# Servo2015_Power_V1_2.net
KiCad netlist of a schematic drawn in EAGLE
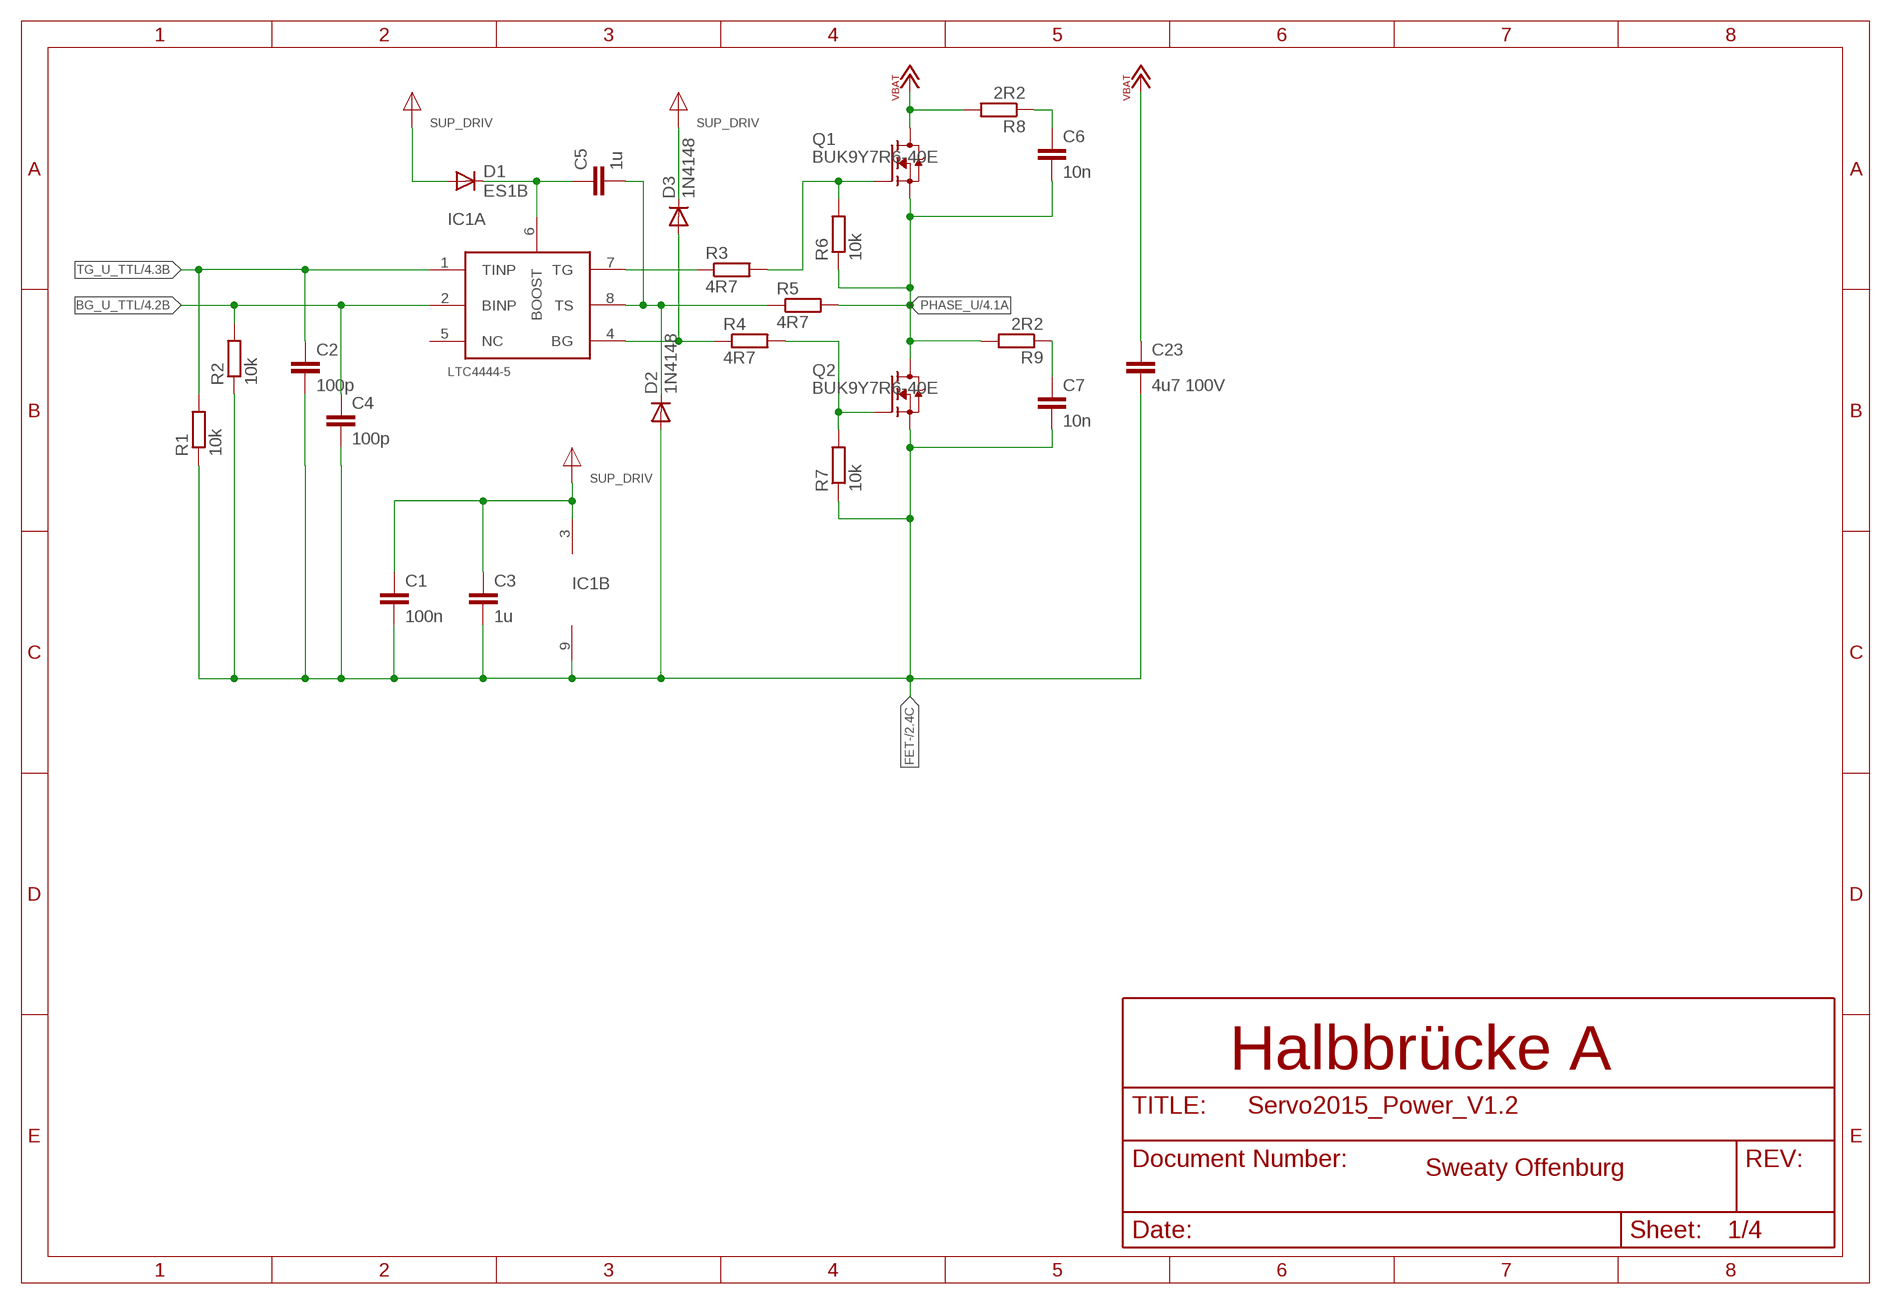
[diagram p0: schematic, sheet 1]
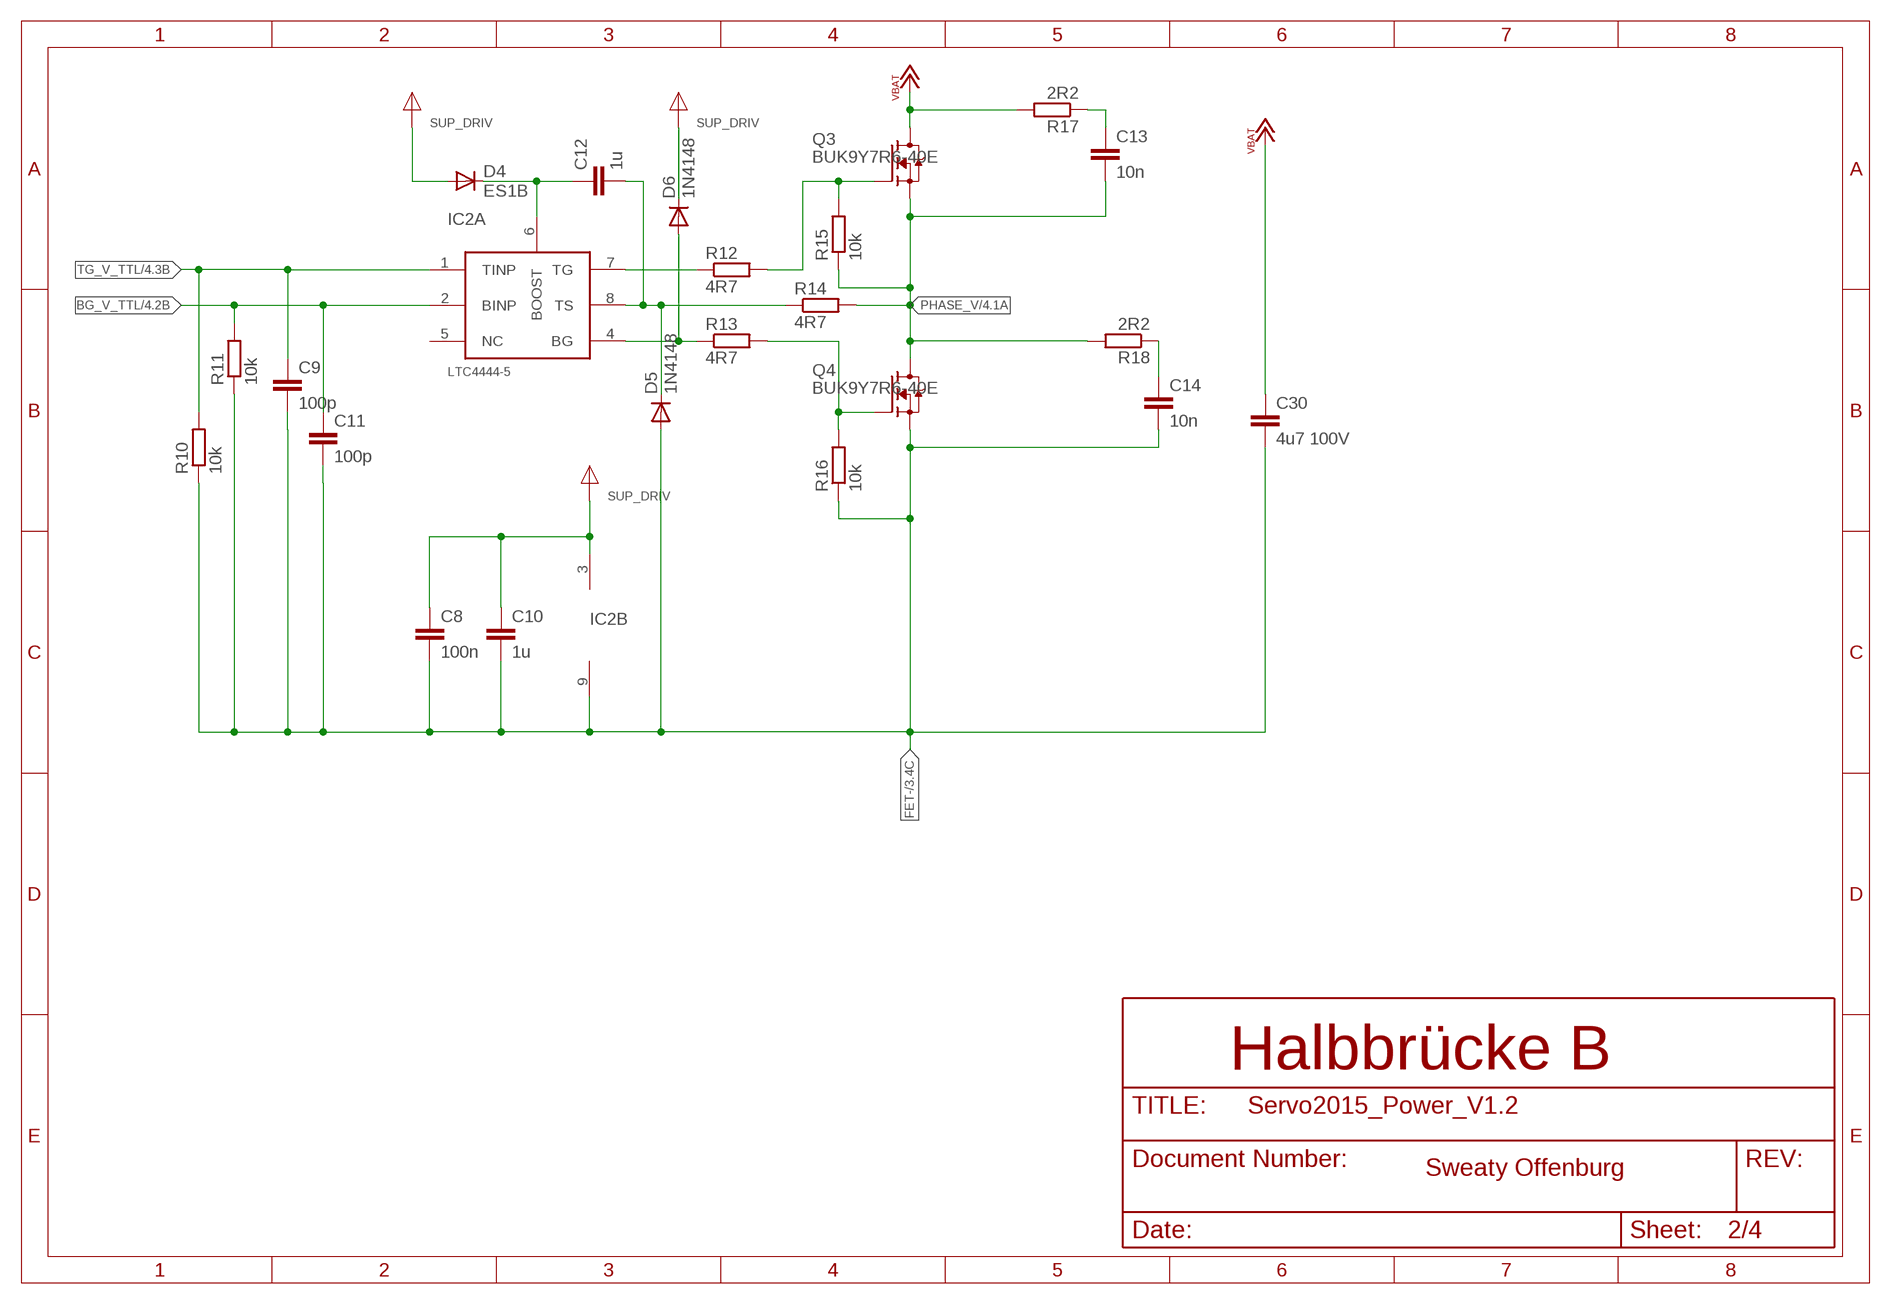
[diagram p1: schematic, sheet 2]
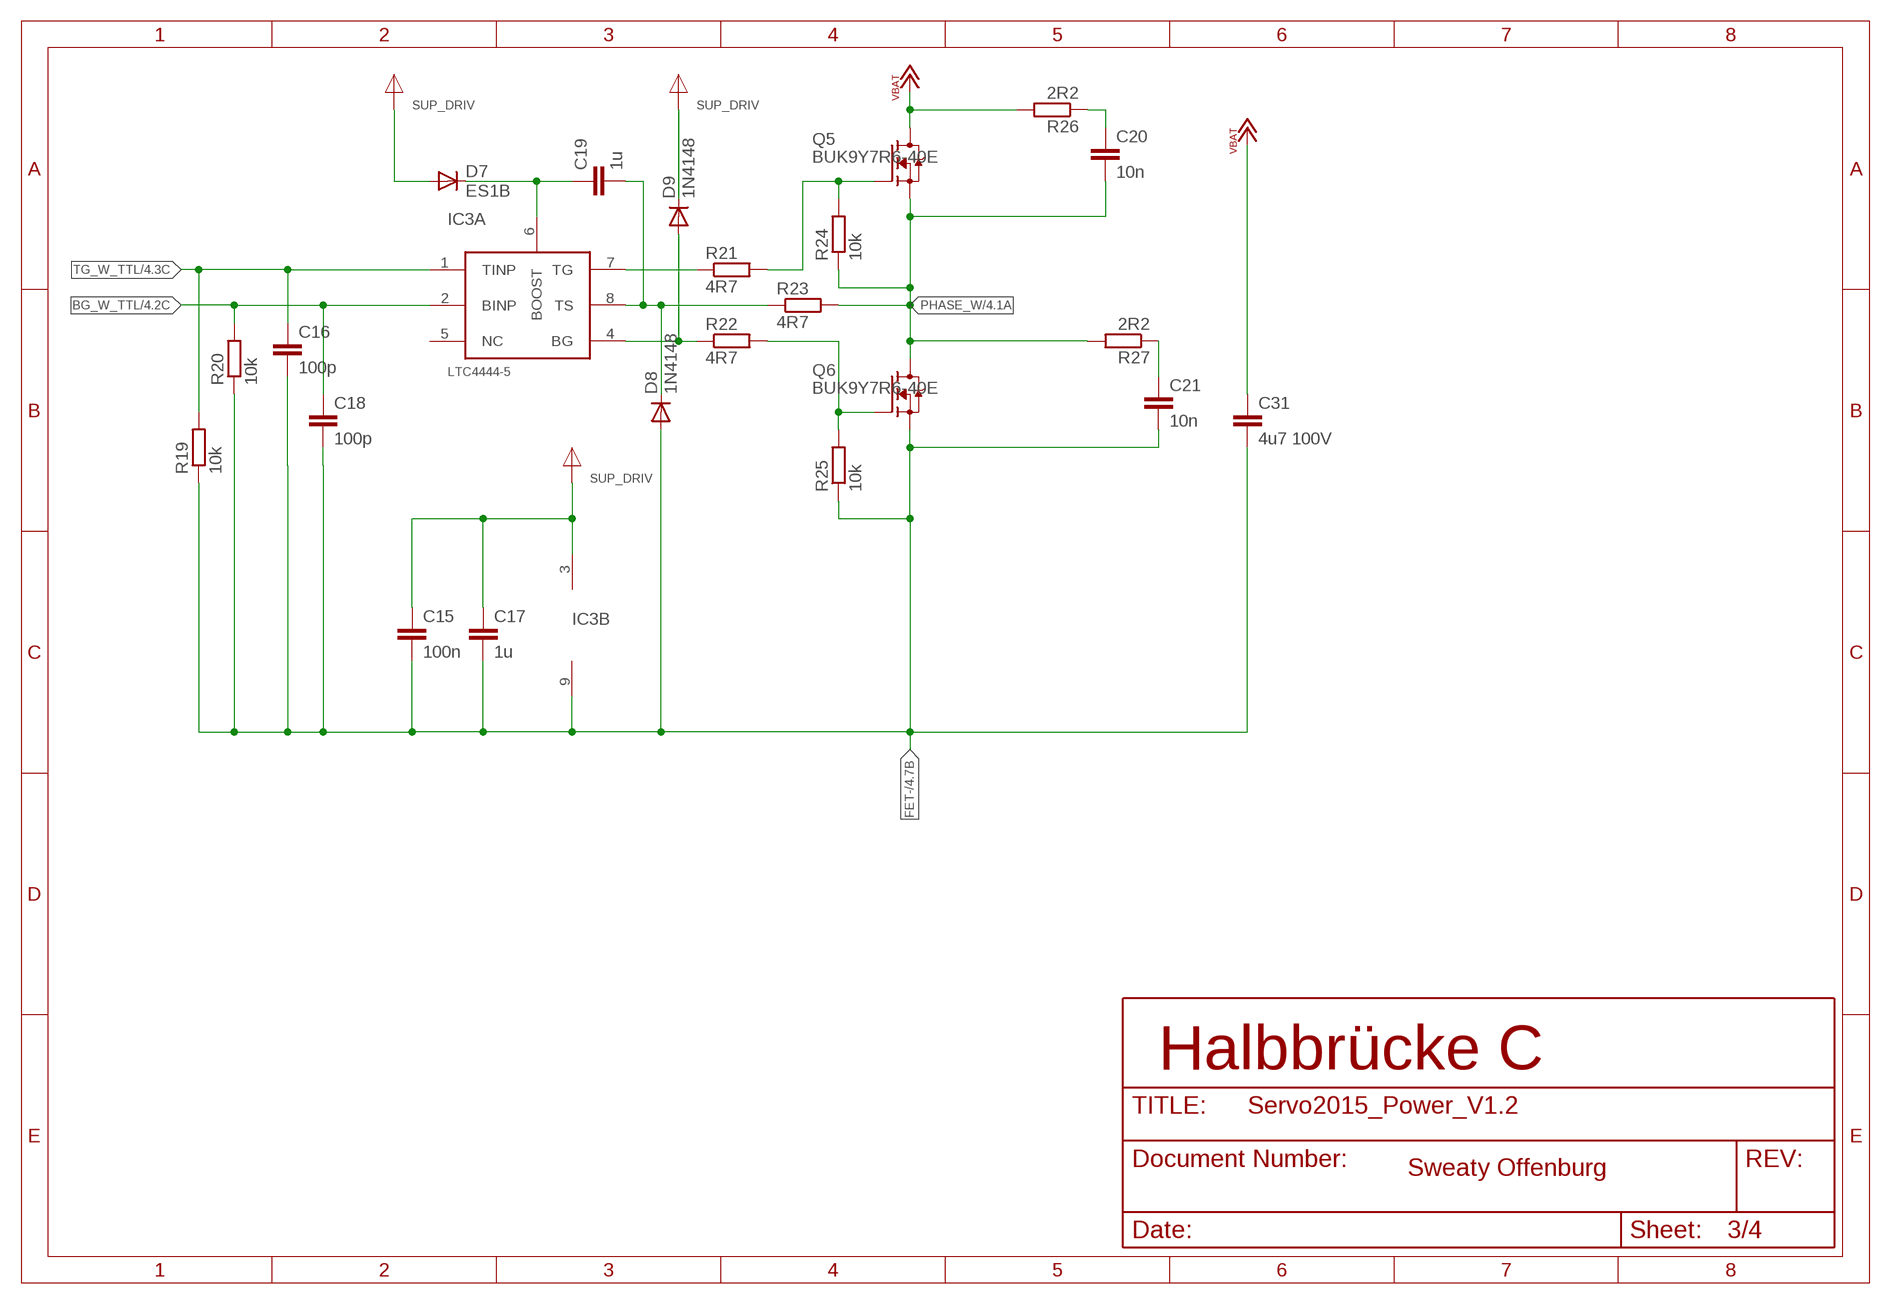
[diagram p2: schematic, sheet 3]
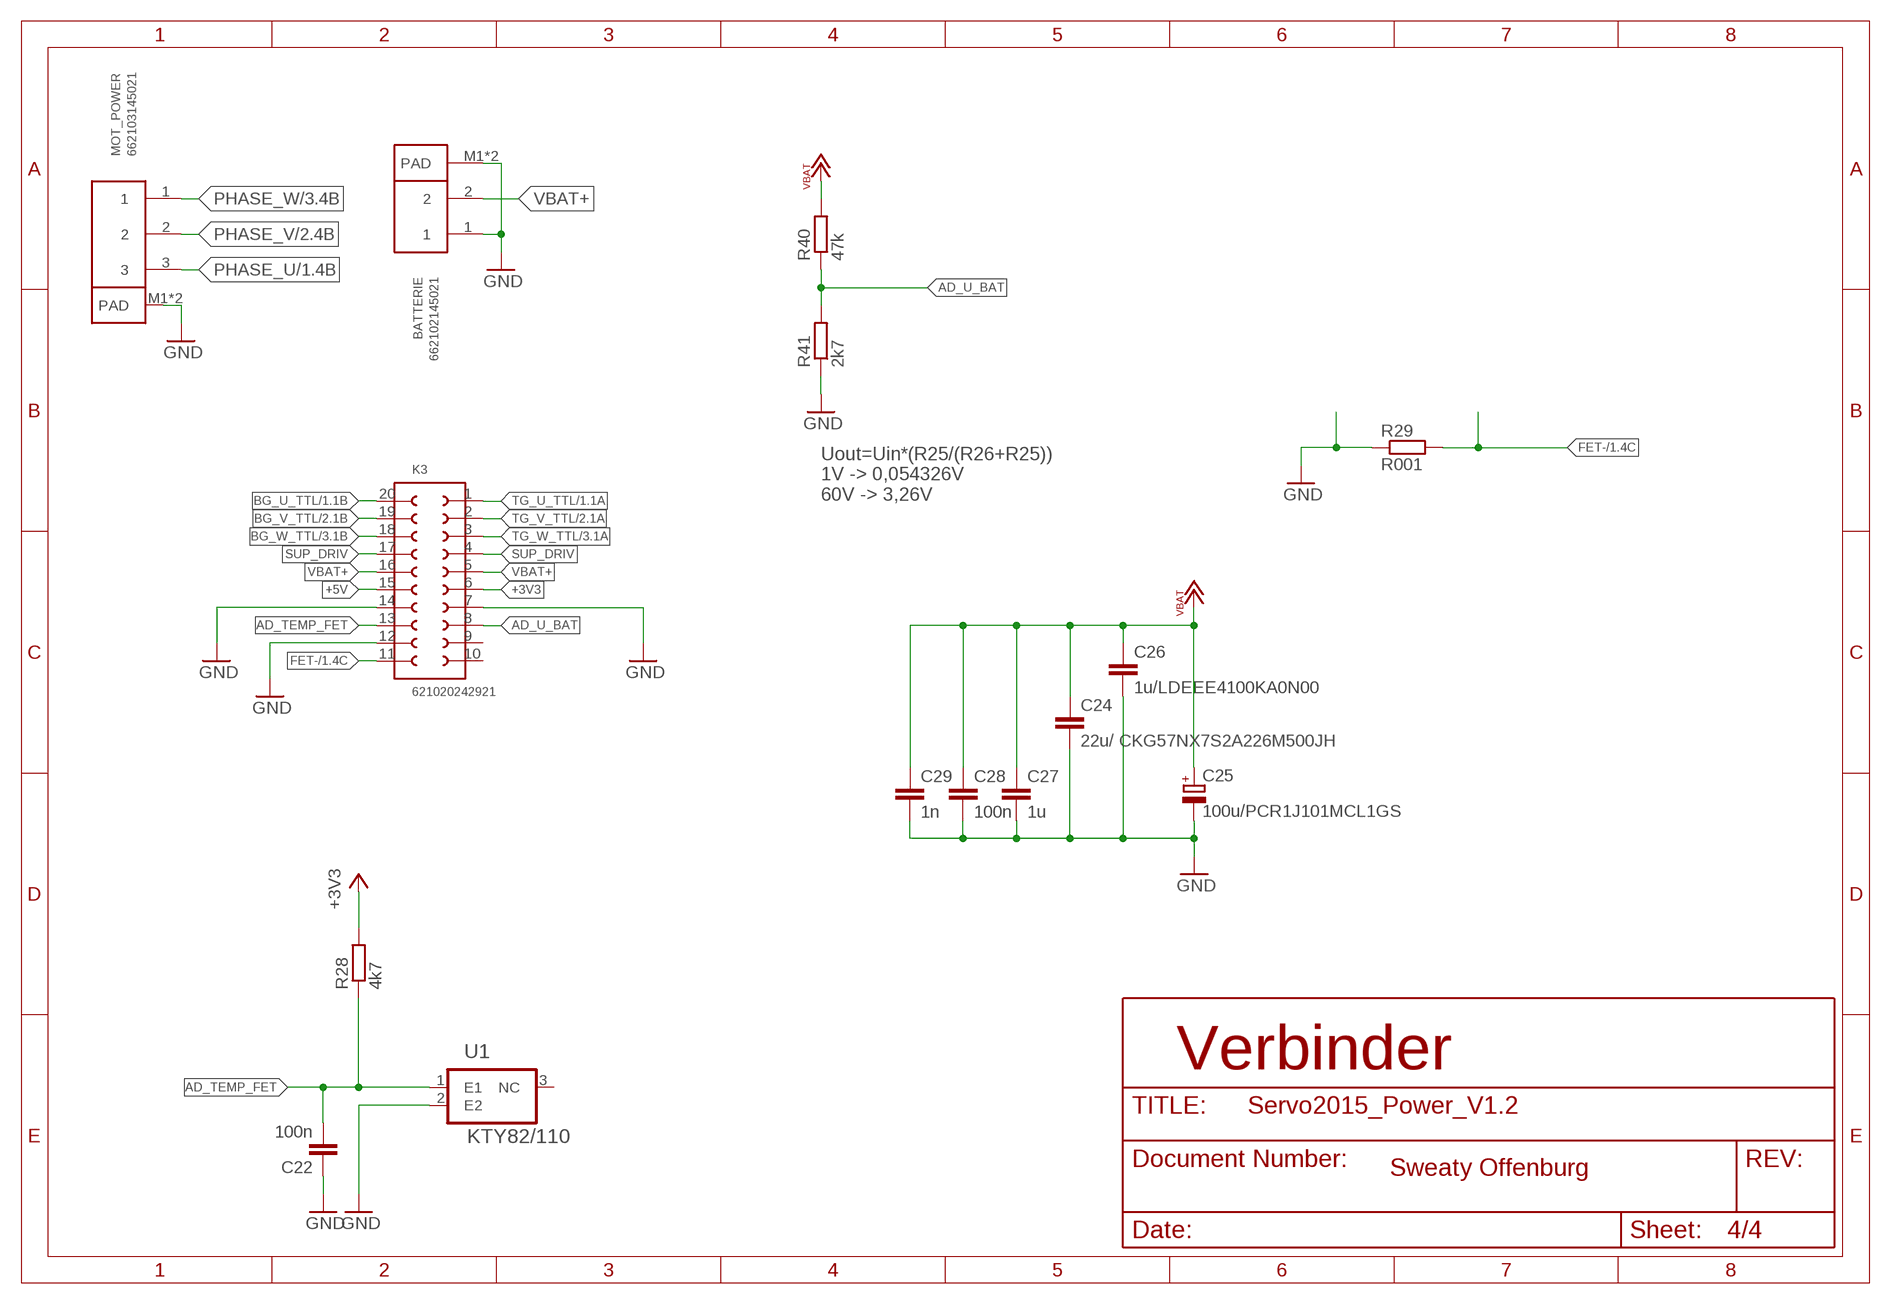
[diagram p3: schematic, sheet 4]

(export (version "E")
  (design (tool "Eeschema 10.0.6"))
  (components
    (comp (ref "C1")
      (value "100n")
      (footprint "eagle-import:C0603")
      (libsource (lib "eagle-import") (part "C-EUC0603"))
    )
    (comp (ref "C2")
      (value "100p")
      (footprint "eagle-import:C0603")
      (libsource (lib "eagle-import") (part "C-EUC0603"))
    )
    (comp (ref "C3")
      (value "1u")
      (footprint "eagle-import:C0603")
      (libsource (lib "eagle-import") (part "C-EUC0603"))
    )
    (comp (ref "C4")
      (value "100p")
      (footprint "eagle-import:C0603")
      (libsource (lib "eagle-import") (part "C-EUC0603"))
    )
    (comp (ref "C5")
      (value "1u")
      (footprint "eagle-import:C0603")
      (libsource (lib "eagle-import") (part "C-EUC0603"))
    )
    (comp (ref "C6")
      (value "10n")
      (footprint "eagle-import:C1210")
      (libsource (lib "eagle-import") (part "C-EUC1210"))
    )
    (comp (ref "C7")
      (value "10n")
      (footprint "eagle-import:C1210")
      (libsource (lib "eagle-import") (part "C-EUC1210"))
    )
    (comp (ref "C23")
      (value "4u7 100V")
      (footprint "eagle-import:C2220K")
      (libsource (lib "eagle-import") (part "C-EUC2220K"))
    )
    (comp (ref "D1")
      (value "ES1B")
      (footprint "eagle-import:DO214AC")
      (libsource (lib "eagle-import") (part "DIODE-DO214AC"))
    )
    (comp (ref "D2")
      (value "1N4148")
      (footprint "eagle-import:SOD123")
      (libsource (lib "eagle-import") (part "DIODE-SOD123"))
    )
    (comp (ref "D3")
      (value "1N4148")
      (footprint "eagle-import:SOD123")
      (libsource (lib "eagle-import") (part "DIODE-SOD123"))
    )
    (comp (ref "IC1")
      (value "LTC4444-5")
      (footprint "eagle-import:MS8E")
      (libsource (lib "eagle-import") (part "LTC4444-5"))
    )
    (comp (ref "Q1")
      (value "BUK9Y7R6-40E")
      (footprint "eagle-import:LFPAK56")
      (libsource (lib "eagle-import") (part "BUK9Y7R6-40E"))
    )
    (comp (ref "Q2")
      (value "BUK9Y7R6-40E")
      (footprint "eagle-import:LFPAK56")
      (libsource (lib "eagle-import") (part "BUK9Y7R6-40E"))
    )
    (comp (ref "R1")
      (value "10k")
      (footprint "eagle-import:R0603")
      (libsource (lib "eagle-import") (part "R-EU_R0603"))
    )
    (comp (ref "R2")
      (value "10k")
      (footprint "eagle-import:R0603")
      (libsource (lib "eagle-import") (part "R-EU_R0603"))
    )
    (comp (ref "R3")
      (value "4R7")
      (footprint "eagle-import:R0805")
      (libsource (lib "eagle-import") (part "R-EU_R0805"))
    )
    (comp (ref "R4")
      (value "4R7")
      (footprint "eagle-import:R0805")
      (libsource (lib "eagle-import") (part "R-EU_R0805"))
    )
    (comp (ref "R5")
      (value "4R7")
      (footprint "eagle-import:R0805")
      (libsource (lib "eagle-import") (part "R-EU_R0805"))
    )
    (comp (ref "R6")
      (value "10k")
      (footprint "eagle-import:R0603")
      (libsource (lib "eagle-import") (part "R-EU_R0603"))
    )
    (comp (ref "R7")
      (value "10k")
      (footprint "eagle-import:R0603")
      (libsource (lib "eagle-import") (part "R-EU_R0603"))
    )
    (comp (ref "R8")
      (value "2R2")
      (footprint "eagle-import:R1206")
      (libsource (lib "eagle-import") (part "R-EU_R1206"))
    )
    (comp (ref "R9")
      (value "2R2")
      (footprint "eagle-import:R1206")
      (libsource (lib "eagle-import") (part "R-EU_R1206"))
    )
    (comp (ref "C8")
      (value "100n")
      (footprint "eagle-import:C0603")
      (libsource (lib "eagle-import") (part "C-EUC0603"))
    )
    (comp (ref "C9")
      (value "100p")
      (footprint "eagle-import:C0603")
      (libsource (lib "eagle-import") (part "C-EUC0603"))
    )
    (comp (ref "C10")
      (value "1u")
      (footprint "eagle-import:C0603")
      (libsource (lib "eagle-import") (part "C-EUC0603"))
    )
    (comp (ref "C11")
      (value "100p")
      (footprint "eagle-import:C0603")
      (libsource (lib "eagle-import") (part "C-EUC0603"))
    )
    (comp (ref "C12")
      (value "1u")
      (footprint "eagle-import:C0603")
      (libsource (lib "eagle-import") (part "C-EUC0603"))
    )
    (comp (ref "C13")
      (value "10n")
      (footprint "eagle-import:C1210")
      (libsource (lib "eagle-import") (part "C-EUC1210"))
    )
    (comp (ref "C14")
      (value "10n")
      (footprint "eagle-import:C1210")
      (libsource (lib "eagle-import") (part "C-EUC1210"))
    )
    (comp (ref "C30")
      (value "4u7 100V")
      (footprint "eagle-import:C2220K")
      (libsource (lib "eagle-import") (part "C-EUC2220K"))
    )
    (comp (ref "D4")
      (value "ES1B")
      (footprint "eagle-import:DO214AC")
      (libsource (lib "eagle-import") (part "DIODE-DO214AC"))
    )
    (comp (ref "D5")
      (value "1N4148")
      (footprint "eagle-import:SOD123")
      (libsource (lib "eagle-import") (part "DIODE-SOD123"))
    )
    (comp (ref "D6")
      (value "1N4148")
      (footprint "eagle-import:SOD123")
      (libsource (lib "eagle-import") (part "DIODE-SOD123"))
    )
    (comp (ref "IC2")
      (value "LTC4444-5")
      (footprint "eagle-import:MS8E")
      (libsource (lib "eagle-import") (part "LTC4444-5"))
    )
    (comp (ref "Q3")
      (value "BUK9Y7R6-40E")
      (footprint "eagle-import:LFPAK56")
      (libsource (lib "eagle-import") (part "BUK9Y7R6-40E"))
    )
    (comp (ref "Q4")
      (value "BUK9Y7R6-40E")
      (footprint "eagle-import:LFPAK56")
      (libsource (lib "eagle-import") (part "BUK9Y7R6-40E"))
    )
    (comp (ref "R10")
      (value "10k")
      (footprint "eagle-import:R0603")
      (libsource (lib "eagle-import") (part "R-EU_R0603"))
    )
    (comp (ref "R11")
      (value "10k")
      (footprint "eagle-import:R0603")
      (libsource (lib "eagle-import") (part "R-EU_R0603"))
    )
    (comp (ref "R12")
      (value "4R7")
      (footprint "eagle-import:R0805")
      (libsource (lib "eagle-import") (part "R-EU_R0805"))
    )
    (comp (ref "R13")
      (value "4R7")
      (footprint "eagle-import:R0805")
      (libsource (lib "eagle-import") (part "R-EU_R0805"))
    )
    (comp (ref "R14")
      (value "4R7")
      (footprint "eagle-import:R0805")
      (libsource (lib "eagle-import") (part "R-EU_R0805"))
    )
    (comp (ref "R15")
      (value "10k")
      (footprint "eagle-import:R0603")
      (libsource (lib "eagle-import") (part "R-EU_R0603"))
    )
    (comp (ref "R16")
      (value "10k")
      (footprint "eagle-import:R0603")
      (libsource (lib "eagle-import") (part "R-EU_R0603"))
    )
    (comp (ref "R17")
      (value "2R2")
      (footprint "eagle-import:R1206")
      (libsource (lib "eagle-import") (part "R-EU_R1206"))
    )
    (comp (ref "R18")
      (value "2R2")
      (footprint "eagle-import:R1206")
      (libsource (lib "eagle-import") (part "R-EU_R1206"))
    )
    (comp (ref "C15")
      (value "100n")
      (footprint "eagle-import:C0603")
      (libsource (lib "eagle-import") (part "C-EUC0603"))
    )
    (comp (ref "C16")
      (value "100p")
      (footprint "eagle-import:C0603")
      (libsource (lib "eagle-import") (part "C-EUC0603"))
    )
    (comp (ref "C17")
      (value "1u")
      (footprint "eagle-import:C0603")
      (libsource (lib "eagle-import") (part "C-EUC0603"))
    )
    (comp (ref "C18")
      (value "100p")
      (footprint "eagle-import:C0603")
      (libsource (lib "eagle-import") (part "C-EUC0603"))
    )
    (comp (ref "C19")
      (value "1u")
      (footprint "eagle-import:C0603")
      (libsource (lib "eagle-import") (part "C-EUC0603"))
    )
    (comp (ref "C20")
      (value "10n")
      (footprint "eagle-import:C1210")
      (libsource (lib "eagle-import") (part "C-EUC1210"))
    )
    (comp (ref "C21")
      (value "10n")
      (footprint "eagle-import:C1210")
      (libsource (lib "eagle-import") (part "C-EUC1210"))
    )
    (comp (ref "C31")
      (value "4u7 100V")
      (footprint "eagle-import:C2220K")
      (libsource (lib "eagle-import") (part "C-EUC2220K"))
    )
    (comp (ref "D7")
      (value "ES1B")
      (footprint "eagle-import:DO214AC")
      (libsource (lib "eagle-import") (part "DIODE-DO214AC"))
    )
    (comp (ref "D8")
      (value "1N4148")
      (footprint "eagle-import:SOD123")
      (libsource (lib "eagle-import") (part "DIODE-SOD123"))
    )
    (comp (ref "D9")
      (value "1N4148")
      (footprint "eagle-import:SOD123")
      (libsource (lib "eagle-import") (part "DIODE-SOD123"))
    )
    (comp (ref "IC3")
      (value "LTC4444-5")
      (footprint "eagle-import:MS8E")
      (libsource (lib "eagle-import") (part "LTC4444-5"))
    )
    (comp (ref "Q5")
      (value "BUK9Y7R6-40E")
      (footprint "eagle-import:LFPAK56")
      (libsource (lib "eagle-import") (part "BUK9Y7R6-40E"))
    )
    (comp (ref "Q6")
      (value "BUK9Y7R6-40E")
      (footprint "eagle-import:LFPAK56")
      (libsource (lib "eagle-import") (part "BUK9Y7R6-40E"))
    )
    (comp (ref "R19")
      (value "10k")
      (footprint "eagle-import:R0603")
      (libsource (lib "eagle-import") (part "R-EU_R0603"))
    )
    (comp (ref "R20")
      (value "10k")
      (footprint "eagle-import:R0603")
      (libsource (lib "eagle-import") (part "R-EU_R0603"))
    )
    (comp (ref "R21")
      (value "4R7")
      (footprint "eagle-import:R0805")
      (libsource (lib "eagle-import") (part "R-EU_R0805"))
    )
    (comp (ref "R22")
      (value "4R7")
      (footprint "eagle-import:R0805")
      (libsource (lib "eagle-import") (part "R-EU_R0805"))
    )
    (comp (ref "R23")
      (value "4R7")
      (footprint "eagle-import:R0805")
      (libsource (lib "eagle-import") (part "R-EU_R0805"))
    )
    (comp (ref "R24")
      (value "10k")
      (footprint "eagle-import:R0603")
      (libsource (lib "eagle-import") (part "R-EU_R0603"))
    )
    (comp (ref "R25")
      (value "10k")
      (footprint "eagle-import:R0603")
      (libsource (lib "eagle-import") (part "R-EU_R0603"))
    )
    (comp (ref "R26")
      (value "2R2")
      (footprint "eagle-import:R1206")
      (libsource (lib "eagle-import") (part "R-EU_R1206"))
    )
    (comp (ref "R27")
      (value "2R2")
      (footprint "eagle-import:R1206")
      (libsource (lib "eagle-import") (part "R-EU_R1206"))
    )
    (comp (ref "BATTERIE")
      (value "662102145021")
      (footprint "eagle-import:662102145021")
      (libsource (lib "eagle-import") (part "662102145021"))
    )
    (comp (ref "C22")
      (value "100n")
      (footprint "eagle-import:C0603")
      (libsource (lib "eagle-import") (part "C-EUC0603"))
    )
    (comp (ref "C24")
      (value "22u/ CKG57NX7S2A226M500JH")
      (footprint "eagle-import:CKG57-5750-CC2220")
      (libsource (lib "eagle-import") (part "C-EUCKG57-5750-CC2220"))
    )
    (comp (ref "C25")
      (value "100u/PCR1J101MCL1GS")
      (footprint "eagle-import:PANASONIC_G")
      (libsource (lib "eagle-import") (part "CPOL-EUG"))
    )
    (comp (ref "C26")
      (value "1u/LDEEE4100KA0N00")
      (footprint "eagle-import:C2824")
      (libsource (lib "eagle-import") (part "C-EUC2824"))
    )
    (comp (ref "C27")
      (value "1u")
      (footprint "eagle-import:C1210")
      (libsource (lib "eagle-import") (part "C-EUC1210"))
    )
    (comp (ref "C28")
      (value "100n")
      (footprint "eagle-import:C0603")
      (libsource (lib "eagle-import") (part "C-EUC0603"))
    )
    (comp (ref "C29")
      (value "1n")
      (footprint "eagle-import:C0603")
      (libsource (lib "eagle-import") (part "C-EUC0603"))
    )
    (comp (ref "K3")
      (value "621020242921")
      (footprint "eagle-import:621020242921")
      (libsource (lib "eagle-import") (part "621020242921"))
    )
    (comp (ref "MOT_POWER")
      (value "662103145021")
      (footprint "eagle-import:662103145021")
      (libsource (lib "eagle-import") (part "662103145021"))
    )
    (comp (ref "R28")
      (value "4k7")
      (footprint "eagle-import:R0603")
      (libsource (lib "eagle-import") (part "R-EU_R0603"))
    )
    (comp (ref "R29")
      (value "R001")
      (footprint "eagle-import:R2512")
      (libsource (lib "eagle-import") (part "R-EU_R2512"))
    )
    (comp (ref "R40")
      (value "47k")
      (footprint "eagle-import:R0603")
      (libsource (lib "eagle-import") (part "R-EU_R0603"))
    )
    (comp (ref "R41")
      (value "2k7")
      (footprint "eagle-import:R0603")
      (libsource (lib "eagle-import") (part "R-EU_R0603"))
    )
    (comp (ref "U1")
      (value "KTY82/110")
      (footprint "eagle-import:SOT95P230X110-3N")
      (libsource (lib "eagle-import") (part "KTY82/110"))
    )
  )
  (nets
    (net (code "1") (name "+3V3") (class "Default")
      (node (ref "K3") (pin "6") (pinfunction "6_6") (pintype "passive"))
      (node (ref "R28") (pin "2") (pinfunction "2_2") (pintype "passive"))
    )
    (net (code "2") (name "+5V") (class "Default")
      (node (ref "K3") (pin "15") (pinfunction "15_15") (pintype "passive"))
    )
    (net (code "3") (name "AD_TEMP_FET") (class "Default")
      (node (ref "C22") (pin "2") (pinfunction "2_2") (pintype "passive"))
      (node (ref "K3") (pin "13") (pinfunction "13_13") (pintype "passive"))
      (node (ref "R28") (pin "1") (pinfunction "1_1") (pintype "passive"))
      (node (ref "U1") (pin "1") (pinfunction "E1_1") (pintype "passive"))
    )
    (net (code "4") (name "AD_U_BAT") (class "Default")
      (node (ref "K3") (pin "8") (pinfunction "8_8") (pintype "passive"))
      (node (ref "R40") (pin "1") (pinfunction "1_1") (pintype "passive"))
      (node (ref "R41") (pin "2") (pinfunction "2_2") (pintype "passive"))
    )
    (net (code "5") (name "BG_U_TTL") (class "Default")
      (node (ref "C4") (pin "1") (pinfunction "1_1") (pintype "passive"))
      (node (ref "IC1") (pin "2") (pinfunction "BINP_2") (pintype "input"))
      (node (ref "K3") (pin "20") (pinfunction "20_20") (pintype "passive"))
      (node (ref "R2") (pin "2") (pinfunction "2_2") (pintype "passive"))
    )
    (net (code "6") (name "BG_V_TTL") (class "Default")
      (node (ref "C11") (pin "1") (pinfunction "1_1") (pintype "passive"))
      (node (ref "IC2") (pin "2") (pinfunction "BINP_2") (pintype "input"))
      (node (ref "K3") (pin "19") (pinfunction "19_19") (pintype "passive"))
      (node (ref "R11") (pin "2") (pinfunction "2_2") (pintype "passive"))
    )
    (net (code "7") (name "BG_W_TTL") (class "Default")
      (node (ref "C18") (pin "1") (pinfunction "1_1") (pintype "passive"))
      (node (ref "IC3") (pin "2") (pinfunction "BINP_2") (pintype "input"))
      (node (ref "K3") (pin "18") (pinfunction "18_18") (pintype "passive"))
      (node (ref "R20") (pin "2") (pinfunction "2_2") (pintype "passive"))
    )
    (net (code "8") (name "FET-") (class "Default")
      (node (ref "C1") (pin "2") (pinfunction "2_2") (pintype "passive"))
      (node (ref "C10") (pin "2") (pinfunction "2_2") (pintype "passive"))
      (node (ref "C11") (pin "2") (pinfunction "2_2") (pintype "passive"))
      (node (ref "C14") (pin "2") (pinfunction "2_2") (pintype "passive"))
      (node (ref "C15") (pin "2") (pinfunction "2_2") (pintype "passive"))
      (node (ref "C16") (pin "2") (pinfunction "2_2") (pintype "passive"))
      (node (ref "C17") (pin "2") (pinfunction "2_2") (pintype "passive"))
      (node (ref "C18") (pin "2") (pinfunction "2_2") (pintype "passive"))
      (node (ref "C2") (pin "2") (pinfunction "2_2") (pintype "passive"))
      (node (ref "C21") (pin "2") (pinfunction "2_2") (pintype "passive"))
      (node (ref "C23") (pin "2") (pinfunction "2_2") (pintype "passive"))
      (node (ref "C3") (pin "2") (pinfunction "2_2") (pintype "passive"))
      (node (ref "C30") (pin "2") (pinfunction "2_2") (pintype "passive"))
      (node (ref "C31") (pin "2") (pinfunction "2_2") (pintype "passive"))
      (node (ref "C4") (pin "2") (pinfunction "2_2") (pintype "passive"))
      (node (ref "C7") (pin "2") (pinfunction "2_2") (pintype "passive"))
      (node (ref "C8") (pin "2") (pinfunction "2_2") (pintype "passive"))
      (node (ref "C9") (pin "2") (pinfunction "2_2") (pintype "passive"))
      (node (ref "D2") (pin "A") (pinfunction "A_A") (pintype "passive"))
      (node (ref "D5") (pin "A") (pinfunction "A_A") (pintype "passive"))
      (node (ref "D8") (pin "A") (pinfunction "A_A") (pintype "passive"))
      (node (ref "IC1") (pin "9") (pinfunction "GND_9") (pintype "power_in"))
      (node (ref "IC2") (pin "9") (pinfunction "GND_9") (pintype "power_in"))
      (node (ref "IC3") (pin "9") (pinfunction "GND_9") (pintype "power_in"))
      (node (ref "K3") (pin "11") (pinfunction "11_11") (pintype "passive"))
      (node (ref "Q2") (pin "1") (pinfunction "S_1") (pintype "passive"))
      (node (ref "Q2") (pin "2") (pinfunction "S_2") (pintype "passive"))
      (node (ref "Q2") (pin "3") (pinfunction "S_3") (pintype "passive"))
      (node (ref "Q4") (pin "1") (pinfunction "S_1") (pintype "passive"))
      (node (ref "Q4") (pin "2") (pinfunction "S_2") (pintype "passive"))
      (node (ref "Q4") (pin "3") (pinfunction "S_3") (pintype "passive"))
      (node (ref "Q6") (pin "1") (pinfunction "S_1") (pintype "passive"))
      (node (ref "Q6") (pin "2") (pinfunction "S_2") (pintype "passive"))
      (node (ref "Q6") (pin "3") (pinfunction "S_3") (pintype "passive"))
      (node (ref "R1") (pin "1") (pinfunction "1_1") (pintype "passive"))
      (node (ref "R10") (pin "1") (pinfunction "1_1") (pintype "passive"))
      (node (ref "R11") (pin "1") (pinfunction "1_1") (pintype "passive"))
      (node (ref "R16") (pin "1") (pinfunction "1_1") (pintype "passive"))
      (node (ref "R19") (pin "1") (pinfunction "1_1") (pintype "passive"))
      (node (ref "R2") (pin "1") (pinfunction "1_1") (pintype "passive"))
      (node (ref "R20") (pin "1") (pinfunction "1_1") (pintype "passive"))
      (node (ref "R25") (pin "1") (pinfunction "1_1") (pintype "passive"))
      (node (ref "R29") (pin "2") (pinfunction "2_2") (pintype "passive"))
      (node (ref "R7") (pin "1") (pinfunction "1_1") (pintype "passive"))
    )
    (net (code "9") (name "GND") (class "Default")
      (node (ref "BATTERIE") (pin "1") (pinfunction "1_1") (pintype "bidirectional"))
      (node (ref "BATTERIE") (pin "M1") (pinfunction "PAD_M1") (pintype "bidirectional"))
      (node (ref "BATTERIE") (pin "M2") (pinfunction "PAD_M2") (pintype "bidirectional"))
      (node (ref "C22") (pin "1") (pinfunction "1_1") (pintype "passive"))
      (node (ref "C24") (pin "2") (pinfunction "2_2") (pintype "passive"))
      (node (ref "C25") (pin "-") (pinfunction "-_-") (pintype "passive"))
      (node (ref "C26") (pin "2") (pinfunction "2_2") (pintype "passive"))
      (node (ref "C27") (pin "2") (pinfunction "2_2") (pintype "passive"))
      (node (ref "C28") (pin "2") (pinfunction "2_2") (pintype "passive"))
      (node (ref "C29") (pin "2") (pinfunction "2_2") (pintype "passive"))
      (node (ref "K3") (pin "12") (pinfunction "12_12") (pintype "passive"))
      (node (ref "K3") (pin "14") (pinfunction "14_14") (pintype "passive"))
      (node (ref "K3") (pin "7") (pinfunction "7_7") (pintype "passive"))
      (node (ref "MOT_POWER") (pin "M1") (pinfunction "PAD_M1") (pintype "bidirectional"))
      (node (ref "MOT_POWER") (pin "M2") (pinfunction "PAD_M2") (pintype "bidirectional"))
      (node (ref "R29") (pin "1") (pinfunction "1_1") (pintype "passive"))
      (node (ref "R41") (pin "1") (pinfunction "1_1") (pintype "passive"))
      (node (ref "U1") (pin "2") (pinfunction "E2_2") (pintype "passive"))
    )
    (net (code "10") (name "Net-(C6-Pad1)") (class "Default")
      (node (ref "C6") (pin "1") (pinfunction "1_1") (pintype "passive"))
      (node (ref "R8") (pin "1") (pinfunction "1_1") (pintype "passive"))
    )
    (net (code "11") (name "Net-(C7-Pad1)") (class "Default")
      (node (ref "C7") (pin "1") (pinfunction "1_1") (pintype "passive"))
      (node (ref "R9") (pin "1") (pinfunction "1_1") (pintype "passive"))
    )
    (net (code "12") (name "Net-(C13-Pad1)") (class "Default")
      (node (ref "C13") (pin "1") (pinfunction "1_1") (pintype "passive"))
      (node (ref "R17") (pin "1") (pinfunction "1_1") (pintype "passive"))
    )
    (net (code "13") (name "Net-(C14-Pad1)") (class "Default")
      (node (ref "C14") (pin "1") (pinfunction "1_1") (pintype "passive"))
      (node (ref "R18") (pin "1") (pinfunction "1_1") (pintype "passive"))
    )
    (net (code "14") (name "Net-(C20-Pad1)") (class "Default")
      (node (ref "C20") (pin "1") (pinfunction "1_1") (pintype "passive"))
      (node (ref "R26") (pin "1") (pinfunction "1_1") (pintype "passive"))
    )
    (net (code "15") (name "Net-(C21-Pad1)") (class "Default")
      (node (ref "C21") (pin "1") (pinfunction "1_1") (pintype "passive"))
      (node (ref "R27") (pin "1") (pinfunction "1_1") (pintype "passive"))
    )
    (net (code "16") (name "Net-(IC1A-BG)") (class "Default")
      (node (ref "D3") (pin "A") (pinfunction "A_A") (pintype "passive"))
      (node (ref "IC1") (pin "4") (pinfunction "BG_4") (pintype "output"))
      (node (ref "R4") (pin "1") (pinfunction "1_1") (pintype "passive"))
    )
    (net (code "17") (name "Net-(IC1A-BOOST)") (class "Default")
      (node (ref "C5") (pin "1") (pinfunction "1_1") (pintype "passive"))
      (node (ref "D1") (pin "C") (pinfunction "C_C") (pintype "passive"))
      (node (ref "IC1") (pin "6") (pinfunction "BOOST_6") (pintype "input"))
    )
    (net (code "18") (name "Net-(IC1A-TG)") (class "Default")
      (node (ref "IC1") (pin "7") (pinfunction "TG_7") (pintype "output"))
      (node (ref "R3") (pin "1") (pinfunction "1_1") (pintype "passive"))
    )
    (net (code "19") (name "Net-(IC1A-TS)") (class "Default")
      (node (ref "C5") (pin "2") (pinfunction "2_2") (pintype "passive"))
      (node (ref "D2") (pin "C") (pinfunction "C_C") (pintype "passive"))
      (node (ref "IC1") (pin "8") (pinfunction "TS_8") (pintype "output"))
      (node (ref "R5") (pin "1") (pinfunction "1_1") (pintype "passive"))
    )
    (net (code "20") (name "Net-(IC2A-BG)") (class "Default")
      (node (ref "D6") (pin "A") (pinfunction "A_A") (pintype "passive"))
      (node (ref "IC2") (pin "4") (pinfunction "BG_4") (pintype "output"))
      (node (ref "R13") (pin "1") (pinfunction "1_1") (pintype "passive"))
    )
    (net (code "21") (name "Net-(IC2A-BOOST)") (class "Default")
      (node (ref "C12") (pin "1") (pinfunction "1_1") (pintype "passive"))
      (node (ref "D4") (pin "C") (pinfunction "C_C") (pintype "passive"))
      (node (ref "IC2") (pin "6") (pinfunction "BOOST_6") (pintype "input"))
    )
    (net (code "22") (name "Net-(IC2A-TG)") (class "Default")
      (node (ref "IC2") (pin "7") (pinfunction "TG_7") (pintype "output"))
      (node (ref "R12") (pin "1") (pinfunction "1_1") (pintype "passive"))
    )
    (net (code "23") (name "Net-(IC2A-TS)") (class "Default")
      (node (ref "C12") (pin "2") (pinfunction "2_2") (pintype "passive"))
      (node (ref "D5") (pin "C") (pinfunction "C_C") (pintype "passive"))
      (node (ref "IC2") (pin "8") (pinfunction "TS_8") (pintype "output"))
      (node (ref "R14") (pin "1") (pinfunction "1_1") (pintype "passive"))
    )
    (net (code "24") (name "Net-(IC3A-BG)") (class "Default")
      (node (ref "D9") (pin "A") (pinfunction "A_A") (pintype "passive"))
      (node (ref "IC3") (pin "4") (pinfunction "BG_4") (pintype "output"))
      (node (ref "R22") (pin "1") (pinfunction "1_1") (pintype "passive"))
    )
    (net (code "25") (name "Net-(IC3A-BOOST)") (class "Default")
      (node (ref "C19") (pin "1") (pinfunction "1_1") (pintype "passive"))
      (node (ref "D7") (pin "C") (pinfunction "C_C") (pintype "passive"))
      (node (ref "IC3") (pin "6") (pinfunction "BOOST_6") (pintype "input"))
    )
    (net (code "26") (name "Net-(IC3A-TG)") (class "Default")
      (node (ref "IC3") (pin "7") (pinfunction "TG_7") (pintype "output"))
      (node (ref "R21") (pin "1") (pinfunction "1_1") (pintype "passive"))
    )
    (net (code "27") (name "Net-(IC3A-TS)") (class "Default")
      (node (ref "C19") (pin "2") (pinfunction "2_2") (pintype "passive"))
      (node (ref "D8") (pin "C") (pinfunction "C_C") (pintype "passive"))
      (node (ref "IC3") (pin "8") (pinfunction "TS_8") (pintype "output"))
      (node (ref "R23") (pin "1") (pinfunction "1_1") (pintype "passive"))
    )
    (net (code "28") (name "Net-(Q1-G)") (class "Default")
      (node (ref "Q1") (pin "4") (pinfunction "G_4") (pintype "passive"))
      (node (ref "R3") (pin "2") (pinfunction "2_2") (pintype "passive"))
      (node (ref "R6") (pin "2") (pinfunction "2_2") (pintype "passive"))
    )
    (net (code "29") (name "Net-(Q2-G)") (class "Default")
      (node (ref "Q2") (pin "4") (pinfunction "G_4") (pintype "passive"))
      (node (ref "R4") (pin "2") (pinfunction "2_2") (pintype "passive"))
      (node (ref "R7") (pin "2") (pinfunction "2_2") (pintype "passive"))
    )
    (net (code "30") (name "Net-(Q3-G)") (class "Default")
      (node (ref "Q3") (pin "4") (pinfunction "G_4") (pintype "passive"))
      (node (ref "R12") (pin "2") (pinfunction "2_2") (pintype "passive"))
      (node (ref "R15") (pin "2") (pinfunction "2_2") (pintype "passive"))
    )
    (net (code "31") (name "Net-(Q4-G)") (class "Default")
      (node (ref "Q4") (pin "4") (pinfunction "G_4") (pintype "passive"))
      (node (ref "R13") (pin "2") (pinfunction "2_2") (pintype "passive"))
      (node (ref "R16") (pin "2") (pinfunction "2_2") (pintype "passive"))
    )
    (net (code "32") (name "Net-(Q5-G)") (class "Default")
      (node (ref "Q5") (pin "4") (pinfunction "G_4") (pintype "passive"))
      (node (ref "R21") (pin "2") (pinfunction "2_2") (pintype "passive"))
      (node (ref "R24") (pin "2") (pinfunction "2_2") (pintype "passive"))
    )
    (net (code "33") (name "Net-(Q6-G)") (class "Default")
      (node (ref "Q6") (pin "4") (pinfunction "G_4") (pintype "passive"))
      (node (ref "R22") (pin "2") (pinfunction "2_2") (pintype "passive"))
      (node (ref "R25") (pin "2") (pinfunction "2_2") (pintype "passive"))
    )
    (net (code "34") (name "PHASE_U") (class "Default")
      (node (ref "C6") (pin "2") (pinfunction "2_2") (pintype "passive"))
      (node (ref "MOT_POWER") (pin "3") (pinfunction "3_3") (pintype "bidirectional"))
      (node (ref "Q1") (pin "1") (pinfunction "S_1") (pintype "passive"))
      (node (ref "Q1") (pin "2") (pinfunction "S_2") (pintype "passive"))
      (node (ref "Q1") (pin "3") (pinfunction "S_3") (pintype "passive"))
      (node (ref "Q2") (pin "5-8") (pinfunction "D_5-8") (pintype "passive"))
      (node (ref "R5") (pin "2") (pinfunction "2_2") (pintype "passive"))
      (node (ref "R6") (pin "1") (pinfunction "1_1") (pintype "passive"))
      (node (ref "R9") (pin "2") (pinfunction "2_2") (pintype "passive"))
    )
    (net (code "35") (name "PHASE_V") (class "Default")
      (node (ref "C13") (pin "2") (pinfunction "2_2") (pintype "passive"))
      (node (ref "MOT_POWER") (pin "2") (pinfunction "2_2") (pintype "bidirectional"))
      (node (ref "Q3") (pin "1") (pinfunction "S_1") (pintype "passive"))
      (node (ref "Q3") (pin "2") (pinfunction "S_2") (pintype "passive"))
      (node (ref "Q3") (pin "3") (pinfunction "S_3") (pintype "passive"))
      (node (ref "Q4") (pin "5-8") (pinfunction "D_5-8") (pintype "passive"))
      (node (ref "R14") (pin "2") (pinfunction "2_2") (pintype "passive"))
      (node (ref "R15") (pin "1") (pinfunction "1_1") (pintype "passive"))
      (node (ref "R18") (pin "2") (pinfunction "2_2") (pintype "passive"))
    )
    (net (code "36") (name "PHASE_W") (class "Default")
      (node (ref "C20") (pin "2") (pinfunction "2_2") (pintype "passive"))
      (node (ref "MOT_POWER") (pin "1") (pinfunction "1_1") (pintype "bidirectional"))
      (node (ref "Q5") (pin "1") (pinfunction "S_1") (pintype "passive"))
      (node (ref "Q5") (pin "2") (pinfunction "S_2") (pintype "passive"))
      (node (ref "Q5") (pin "3") (pinfunction "S_3") (pintype "passive"))
      (node (ref "Q6") (pin "5-8") (pinfunction "D_5-8") (pintype "passive"))
      (node (ref "R23") (pin "2") (pinfunction "2_2") (pintype "passive"))
      (node (ref "R24") (pin "1") (pinfunction "1_1") (pintype "passive"))
      (node (ref "R27") (pin "2") (pinfunction "2_2") (pintype "passive"))
    )
    (net (code "37") (name "SUP_DRIV") (class "Default")
      (node (ref "C1") (pin "1") (pinfunction "1_1") (pintype "passive"))
      (node (ref "C10") (pin "1") (pinfunction "1_1") (pintype "passive"))
      (node (ref "C15") (pin "1") (pinfunction "1_1") (pintype "passive"))
      (node (ref "C17") (pin "1") (pinfunction "1_1") (pintype "passive"))
      (node (ref "C3") (pin "1") (pinfunction "1_1") (pintype "passive"))
      (node (ref "C8") (pin "1") (pinfunction "1_1") (pintype "passive"))
      (node (ref "D1") (pin "A") (pinfunction "A_A") (pintype "passive"))
      (node (ref "D3") (pin "C") (pinfunction "C_C") (pintype "passive"))
      (node (ref "D4") (pin "A") (pinfunction "A_A") (pintype "passive"))
      (node (ref "D6") (pin "C") (pinfunction "C_C") (pintype "passive"))
      (node (ref "D7") (pin "A") (pinfunction "A_A") (pintype "passive"))
      (node (ref "D9") (pin "C") (pinfunction "C_C") (pintype "passive"))
      (node (ref "IC1") (pin "3") (pinfunction "VCC_3") (pintype "power_in"))
      (node (ref "IC2") (pin "3") (pinfunction "VCC_3") (pintype "power_in"))
      (node (ref "IC3") (pin "3") (pinfunction "VCC_3") (pintype "power_in"))
      (node (ref "K3") (pin "17") (pinfunction "17_17") (pintype "passive"))
      (node (ref "K3") (pin "4") (pinfunction "4_4") (pintype "passive"))
    )
    (net (code "38") (name "TG_U_TTL") (class "Default")
      (node (ref "C2") (pin "1") (pinfunction "1_1") (pintype "passive"))
      (node (ref "IC1") (pin "1") (pinfunction "TINP_1") (pintype "input"))
      (node (ref "K3") (pin "1") (pinfunction "1_1") (pintype "passive"))
      (node (ref "R1") (pin "2") (pinfunction "2_2") (pintype "passive"))
    )
    (net (code "39") (name "TG_V_TTL") (class "Default")
      (node (ref "C9") (pin "1") (pinfunction "1_1") (pintype "passive"))
      (node (ref "IC2") (pin "1") (pinfunction "TINP_1") (pintype "input"))
      (node (ref "K3") (pin "2") (pinfunction "2_2") (pintype "passive"))
      (node (ref "R10") (pin "2") (pinfunction "2_2") (pintype "passive"))
    )
    (net (code "40") (name "TG_W_TTL") (class "Default")
      (node (ref "C16") (pin "1") (pinfunction "1_1") (pintype "passive"))
      (node (ref "IC3") (pin "1") (pinfunction "TINP_1") (pintype "input"))
      (node (ref "K3") (pin "3") (pinfunction "3_3") (pintype "passive"))
      (node (ref "R19") (pin "2") (pinfunction "2_2") (pintype "passive"))
    )
    (net (code "41") (name "VBAT+") (class "Default")
      (node (ref "BATTERIE") (pin "2") (pinfunction "2_2") (pintype "bidirectional"))
      (node (ref "C23") (pin "1") (pinfunction "1_1") (pintype "passive"))
      (node (ref "C24") (pin "1") (pinfunction "1_1") (pintype "passive"))
      (node (ref "C25") (pin "+") (pinfunction "+_+") (pintype "passive"))
      (node (ref "C26") (pin "1") (pinfunction "1_1") (pintype "passive"))
      (node (ref "C27") (pin "1") (pinfunction "1_1") (pintype "passive"))
      (node (ref "C28") (pin "1") (pinfunction "1_1") (pintype "passive"))
      (node (ref "C29") (pin "1") (pinfunction "1_1") (pintype "passive"))
      (node (ref "C30") (pin "1") (pinfunction "1_1") (pintype "passive"))
      (node (ref "C31") (pin "1") (pinfunction "1_1") (pintype "passive"))
      (node (ref "K3") (pin "16") (pinfunction "16_16") (pintype "passive"))
      (node (ref "K3") (pin "5") (pinfunction "5_5") (pintype "passive"))
      (node (ref "Q1") (pin "5-8") (pinfunction "D_5-8") (pintype "passive"))
      (node (ref "Q3") (pin "5-8") (pinfunction "D_5-8") (pintype "passive"))
      (node (ref "Q5") (pin "5-8") (pinfunction "D_5-8") (pintype "passive"))
      (node (ref "R17") (pin "2") (pinfunction "2_2") (pintype "passive"))
      (node (ref "R26") (pin "2") (pinfunction "2_2") (pintype "passive"))
      (node (ref "R40") (pin "2") (pinfunction "2_2") (pintype "passive"))
      (node (ref "R8") (pin "2") (pinfunction "2_2") (pintype "passive"))
    )
    (net (code "42") (name "unconnected-(IC1A-NC-Pad5)") (class "Default")
      (node (ref "IC1") (pin "5") (pinfunction "NC_5") (pintype "no_connect"))
    )
    (net (code "43") (name "unconnected-(IC2A-NC-Pad5)") (class "Default")
      (node (ref "IC2") (pin "5") (pinfunction "NC_5") (pintype "no_connect"))
    )
    (net (code "44") (name "unconnected-(IC3A-NC-Pad5)") (class "Default")
      (node (ref "IC3") (pin "5") (pinfunction "NC_5") (pintype "no_connect"))
    )
    (net (code "45") (name "unconnected-(K3-Pad9)") (class "Default")
      (node (ref "K3") (pin "9") (pinfunction "9_9") (pintype "passive"))
    )
    (net (code "46") (name "unconnected-(K3-Pad10)") (class "Default")
      (node (ref "K3") (pin "10") (pinfunction "10_10") (pintype "passive"))
    )
    (net (code "47") (name "unconnected-(U1-NC-Pad3)") (class "Default")
      (node (ref "U1") (pin "3") (pinfunction "NC_3") (pintype "passive"))
    )
  )
)
